# SplitFlap.net
KiCad netlist of a schematic drawn in EAGLE
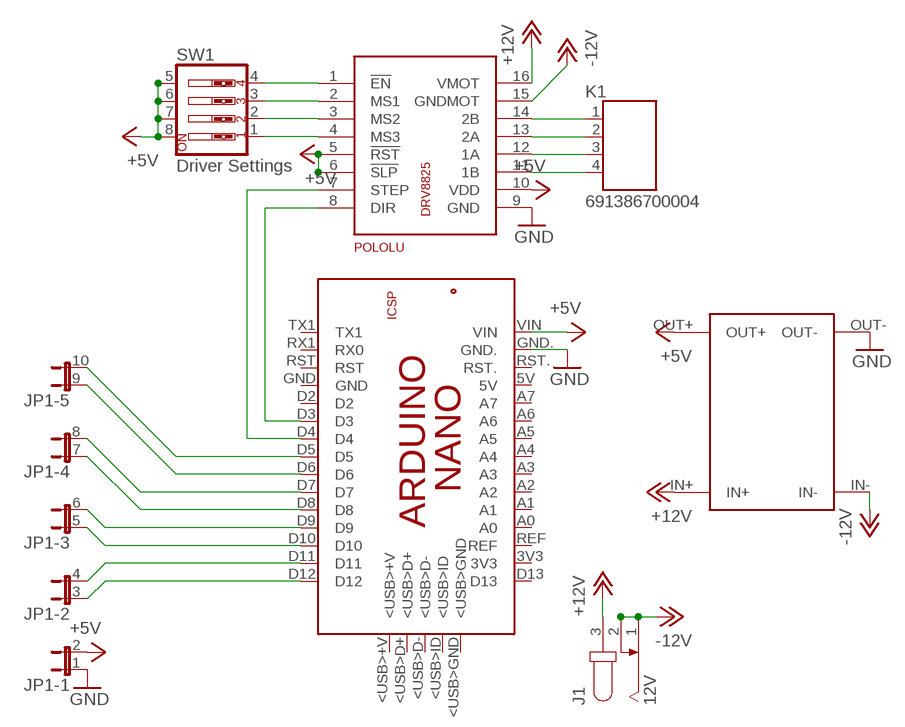
[diagram p0: schematic, sheet 1]

(export (version "E")
  (design (tool "Eeschema 10.0.6"))
  (components
    (comp (ref "J1")
      (value "12V")
      (footprint "eagle-import:SPC4077")
      (libsource (lib "eagle-import") (part "JACK-PLUG0"))
    )
    (comp (ref "JP1")
      (value "JP5QE")
      (footprint "eagle-import:JP5Q")
      (libsource (lib "eagle-import") (part "JP5QE"))
    )
    (comp (ref "K1")
      (value "691386700004")
      (footprint "eagle-import:691386700004")
      (libsource (lib "eagle-import") (part "691386700004"))
    )
    (comp (ref "LEIVIN")
      (value "LEIVIN_PWR")
      (footprint "eagle-import:LEIVIN_PWR")
      (libsource (lib "eagle-import") (part "LEIVIN_PWR"))
    )
    (comp (ref "PCB1")
      (value "ARDUINO_NANO")
      (footprint "eagle-import:ARDUINO_NANO")
      (libsource (lib "eagle-import") (part "ARDUINO_NANO"))
    )
    (comp (ref "POLOLU")
      (value "DRV8825")
      (footprint "eagle-import:DIP16")
      (libsource (lib "eagle-import") (part "DRV8825"))
    )
    (comp (ref "SW1")
      (value "Driver Settings")
      (footprint "eagle-import:EDG-04")
      (libsource (lib "eagle-import") (part "SW_DIP-4"))
    )
  )
  (nets
    (net (code "1") (name "+5V") (class "Default")
      (node (ref "JP1") (pin "2") (pinfunction "2_2") (pintype "passive"))
      (node (ref "LEIVIN") (pin "OUT+") (pinfunction "OUT+_OUT+") (pintype "power_in"))
      (node (ref "PCB1") (pin "VIN") (pinfunction "VIN_VIN") (pintype "bidirectional"))
      (node (ref "POLOLU") (pin "10") (pinfunction "VDD_10") (pintype "power_in"))
      (node (ref "POLOLU") (pin "5") (pinfunction "~{RST}_5") (pintype "input"))
      (node (ref "POLOLU") (pin "6") (pinfunction "~{SLP}_6") (pintype "input"))
      (node (ref "SW1") (pin "5") (pinfunction "5_5") (pintype "passive"))
      (node (ref "SW1") (pin "6") (pinfunction "6_6") (pintype "passive"))
      (node (ref "SW1") (pin "7") (pinfunction "7_7") (pintype "passive"))
      (node (ref "SW1") (pin "8") (pinfunction "8_8") (pintype "passive"))
    )
    (net (code "2") (name "+12V") (class "Default")
      (node (ref "J1") (pin "3") (pinfunction "3_3") (pintype "passive"))
      (node (ref "LEIVIN") (pin "IN+") (pinfunction "IN+_IN+") (pintype "power_in"))
      (node (ref "POLOLU") (pin "16") (pinfunction "VMOT_16") (pintype "power_in"))
    )
    (net (code "3") (name "-12V") (class "Default")
      (node (ref "J1") (pin "1") (pinfunction "1_1") (pintype "passive"))
      (node (ref "J1") (pin "2") (pinfunction "2_2") (pintype "passive"))
      (node (ref "LEIVIN") (pin "IN-") (pinfunction "IN-_IN-") (pintype "power_in"))
      (node (ref "POLOLU") (pin "15") (pinfunction "GNDMOT_15") (pintype "power_in"))
    )
    (net (code "4") (name "GND") (class "Default")
      (node (ref "JP1") (pin "1") (pinfunction "1_1") (pintype "passive"))
      (node (ref "LEIVIN") (pin "OUT-") (pinfunction "OUT-_OUT-") (pintype "power_in"))
      (node (ref "PCB1") (pin "GND.") (pinfunction "GND._GND.") (pintype "bidirectional"))
      (node (ref "POLOLU") (pin "9") (pinfunction "GND_9") (pintype "power_in"))
    )
    (net (code "5") (name "Net-(JP1B-1)") (class "Default")
      (node (ref "JP1") (pin "3") (pinfunction "1_3") (pintype "passive"))
      (node (ref "PCB1") (pin "D12") (pinfunction "D12_D12") (pintype "bidirectional"))
    )
    (net (code "6") (name "Net-(JP1B-2)") (class "Default")
      (node (ref "JP1") (pin "4") (pinfunction "2_4") (pintype "passive"))
      (node (ref "PCB1") (pin "D11") (pinfunction "D11_D11") (pintype "bidirectional"))
    )
    (net (code "7") (name "Net-(JP1C-1)") (class "Default")
      (node (ref "JP1") (pin "5") (pinfunction "1_5") (pintype "passive"))
      (node (ref "PCB1") (pin "D10") (pinfunction "D10_D10") (pintype "bidirectional"))
    )
    (net (code "8") (name "Net-(JP1C-2)") (class "Default")
      (node (ref "JP1") (pin "6") (pinfunction "2_6") (pintype "passive"))
      (node (ref "PCB1") (pin "D9") (pinfunction "D9_D9") (pintype "bidirectional"))
    )
    (net (code "9") (name "Net-(JP1D-1)") (class "Default")
      (node (ref "JP1") (pin "7") (pinfunction "1_7") (pintype "passive"))
      (node (ref "PCB1") (pin "D8") (pinfunction "D8_D8") (pintype "bidirectional"))
    )
    (net (code "10") (name "Net-(JP1D-2)") (class "Default")
      (node (ref "JP1") (pin "8") (pinfunction "2_8") (pintype "passive"))
      (node (ref "PCB1") (pin "D7") (pinfunction "D7_D7") (pintype "bidirectional"))
    )
    (net (code "11") (name "Net-(JP1E-1)") (class "Default")
      (node (ref "JP1") (pin "9") (pinfunction "1_9") (pintype "passive"))
      (node (ref "PCB1") (pin "D6") (pinfunction "D6_D6") (pintype "bidirectional"))
    )
    (net (code "12") (name "Net-(JP1E-2)") (class "Default")
      (node (ref "JP1") (pin "10") (pinfunction "2_10") (pintype "passive"))
      (node (ref "PCB1") (pin "D5") (pinfunction "D5_D5") (pintype "bidirectional"))
    )
    (net (code "13") (name "Net-(POLOLU-1A)") (class "Default")
      (node (ref "K1") (pin "3") (pinfunction "3_3") (pintype "passive"))
      (node (ref "POLOLU") (pin "12") (pinfunction "1A_12") (pintype "output"))
    )
    (net (code "14") (name "Net-(POLOLU-1B)") (class "Default")
      (node (ref "K1") (pin "4") (pinfunction "4_4") (pintype "passive"))
      (node (ref "POLOLU") (pin "11") (pinfunction "1B_11") (pintype "output"))
    )
    (net (code "15") (name "Net-(POLOLU-2A)") (class "Default")
      (node (ref "K1") (pin "2") (pinfunction "2_2") (pintype "passive"))
      (node (ref "POLOLU") (pin "13") (pinfunction "2A_13") (pintype "output"))
    )
    (net (code "16") (name "Net-(POLOLU-2B)") (class "Default")
      (node (ref "K1") (pin "1") (pinfunction "1_1") (pintype "passive"))
      (node (ref "POLOLU") (pin "14") (pinfunction "2B_14") (pintype "output"))
    )
    (net (code "17") (name "Net-(POLOLU-DIR)") (class "Default")
      (node (ref "PCB1") (pin "D3") (pinfunction "D3_D3") (pintype "bidirectional"))
      (node (ref "POLOLU") (pin "8") (pinfunction "DIR_8") (pintype "input"))
    )
    (net (code "18") (name "Net-(POLOLU-MS1)") (class "Default")
      (node (ref "POLOLU") (pin "2") (pinfunction "MS1_2") (pintype "input"))
      (node (ref "SW1") (pin "3") (pinfunction "3_3") (pintype "passive"))
    )
    (net (code "19") (name "Net-(POLOLU-MS2)") (class "Default")
      (node (ref "POLOLU") (pin "3") (pinfunction "MS2_3") (pintype "input"))
      (node (ref "SW1") (pin "2") (pinfunction "2_2") (pintype "passive"))
    )
    (net (code "20") (name "Net-(POLOLU-MS3)") (class "Default")
      (node (ref "POLOLU") (pin "4") (pinfunction "MS3_4") (pintype "input"))
      (node (ref "SW1") (pin "1") (pinfunction "1_1") (pintype "passive"))
    )
    (net (code "21") (name "Net-(POLOLU-STEP)") (class "Default")
      (node (ref "PCB1") (pin "D4") (pinfunction "D4_D4") (pintype "bidirectional"))
      (node (ref "POLOLU") (pin "7") (pinfunction "STEP_7") (pintype "input"))
    )
    (net (code "22") (name "Net-(POLOLU-~{EN})") (class "Default")
      (node (ref "POLOLU") (pin "1") (pinfunction "~{EN}_1") (pintype "input"))
      (node (ref "SW1") (pin "4") (pinfunction "4_4") (pintype "passive"))
    )
    (net (code "23") (name "unconnected-(PCB1-Pad3V3)") (class "Default")
      (node (ref "PCB1") (pin "3V3") (pinfunction "3V3_3V3") (pintype "bidirectional"))
    )
    (net (code "24") (name "unconnected-(PCB1-Pad5V)") (class "Default")
      (node (ref "PCB1") (pin "5V") (pinfunction "5V_5V") (pintype "bidirectional"))
    )
    (net (code "25") (name "unconnected-(PCB1-Pad5V.)") (class "Default")
      (node (ref "PCB1") (pin "5V.") (pinfunction "5V._5V.") (pintype "bidirectional"))
    )
    (net (code "26") (name "unconnected-(PCB1-Pad<USB>+V)") (class "Default")
      (node (ref "PCB1") (pin "<USB>+V") (pinfunction "<USB>+V_<USB>+V") (pintype "bidirectional"))
    )
    (net (code "27") (name "unconnected-(PCB1-Pad<USB>D+)") (class "Default")
      (node (ref "PCB1") (pin "<USB>D+") (pinfunction "<USB>D+_<USB>D+") (pintype "bidirectional"))
    )
    (net (code "28") (name "unconnected-(PCB1-Pad<USB>D-)") (class "Default")
      (node (ref "PCB1") (pin "<USB>D-") (pinfunction "<USB>D-_<USB>D-") (pintype "bidirectional"))
    )
    (net (code "29") (name "unconnected-(PCB1-Pad<USB>GND)") (class "Default")
      (node (ref "PCB1") (pin "<USB>GND") (pinfunction "<USB>GND_<USB>GND") (pintype "bidirectional"))
    )
    (net (code "30") (name "unconnected-(PCB1-Pad<USB>ID)") (class "Default")
      (node (ref "PCB1") (pin "<USB>ID") (pinfunction "<USB>ID_<USB>ID") (pintype "bidirectional"))
    )
    (net (code "31") (name "unconnected-(PCB1-PadA0)") (class "Default")
      (node (ref "PCB1") (pin "A0") (pinfunction "A0_A0") (pintype "bidirectional"))
    )
    (net (code "32") (name "unconnected-(PCB1-PadA1)") (class "Default")
      (node (ref "PCB1") (pin "A1") (pinfunction "A1_A1") (pintype "bidirectional"))
    )
    (net (code "33") (name "unconnected-(PCB1-PadA2)") (class "Default")
      (node (ref "PCB1") (pin "A2") (pinfunction "A2_A2") (pintype "bidirectional"))
    )
    (net (code "34") (name "unconnected-(PCB1-PadA3)") (class "Default")
      (node (ref "PCB1") (pin "A3") (pinfunction "A3_A3") (pintype "bidirectional"))
    )
    (net (code "35") (name "unconnected-(PCB1-PadA4)") (class "Default")
      (node (ref "PCB1") (pin "A4") (pinfunction "A4_A4") (pintype "bidirectional"))
    )
    (net (code "36") (name "unconnected-(PCB1-PadA5)") (class "Default")
      (node (ref "PCB1") (pin "A5") (pinfunction "A5_A5") (pintype "bidirectional"))
    )
    (net (code "37") (name "unconnected-(PCB1-PadA6)") (class "Default")
      (node (ref "PCB1") (pin "A6") (pinfunction "A6_A6") (pintype "bidirectional"))
    )
    (net (code "38") (name "unconnected-(PCB1-PadA7)") (class "Default")
      (node (ref "PCB1") (pin "A7") (pinfunction "A7_A7") (pintype "bidirectional"))
    )
    (net (code "39") (name "unconnected-(PCB1-PadD2)") (class "Default")
      (node (ref "PCB1") (pin "D2") (pinfunction "D2_D2") (pintype "bidirectional"))
    )
    (net (code "40") (name "unconnected-(PCB1-PadD13)") (class "Default")
      (node (ref "PCB1") (pin "D13") (pinfunction "D13_D13") (pintype "bidirectional"))
    )
    (net (code "41") (name "unconnected-(PCB1-PadGND)") (class "Default")
      (node (ref "PCB1") (pin "GND") (pinfunction "GND_GND") (pintype "bidirectional"))
    )
    (net (code "42") (name "unconnected-(PCB1-PadGND_)") (class "Default")
      (node (ref "PCB1") (pin "GND_") (pinfunction "GND__GND_") (pintype "bidirectional"))
    )
    (net (code "43") (name "unconnected-(PCB1-PadMISO)") (class "Default")
      (node (ref "PCB1") (pin "MISO") (pinfunction "MISO_MISO") (pintype "bidirectional"))
    )
    (net (code "44") (name "unconnected-(PCB1-PadMOSI)") (class "Default")
      (node (ref "PCB1") (pin "MOSI") (pinfunction "MOSI_MOSI") (pintype "bidirectional"))
    )
    (net (code "45") (name "unconnected-(PCB1-PadREF)") (class "Default")
      (node (ref "PCB1") (pin "REF") (pinfunction "REF_REF") (pintype "bidirectional"))
    )
    (net (code "46") (name "unconnected-(PCB1-PadRESET..)") (class "Default")
      (node (ref "PCB1") (pin "RESET..") (pinfunction "RESET.._RESET..") (pintype "bidirectional"))
    )
    (net (code "47") (name "unconnected-(PCB1-PadRST)") (class "Default")
      (node (ref "PCB1") (pin "RST") (pinfunction "RST_RST") (pintype "bidirectional"))
    )
    (net (code "48") (name "unconnected-(PCB1-PadRST.)") (class "Default")
      (node (ref "PCB1") (pin "RST.") (pinfunction "RST._RST.") (pintype "bidirectional"))
    )
    (net (code "49") (name "unconnected-(PCB1-PadSCK)") (class "Default")
      (node (ref "PCB1") (pin "SCK") (pinfunction "SCK_SCK") (pintype "bidirectional"))
    )
    (net (code "50") (name "unconnected-(PCB1-PadTX1)") (class "Default")
      (node (ref "PCB1") (pin "TX1") (pinfunction "TX1_TX1") (pintype "bidirectional"))
    )
    (net (code "51") (name "unconnected-(PCB1-RX0-PadRX1)") (class "Default")
      (node (ref "PCB1") (pin "RX1") (pinfunction "RX0_RX1") (pintype "bidirectional"))
    )
  )
)
